# RollerShutterNode_nrf_1-1_EN.net
KiCad netlist of a schematic drawn in EAGLE
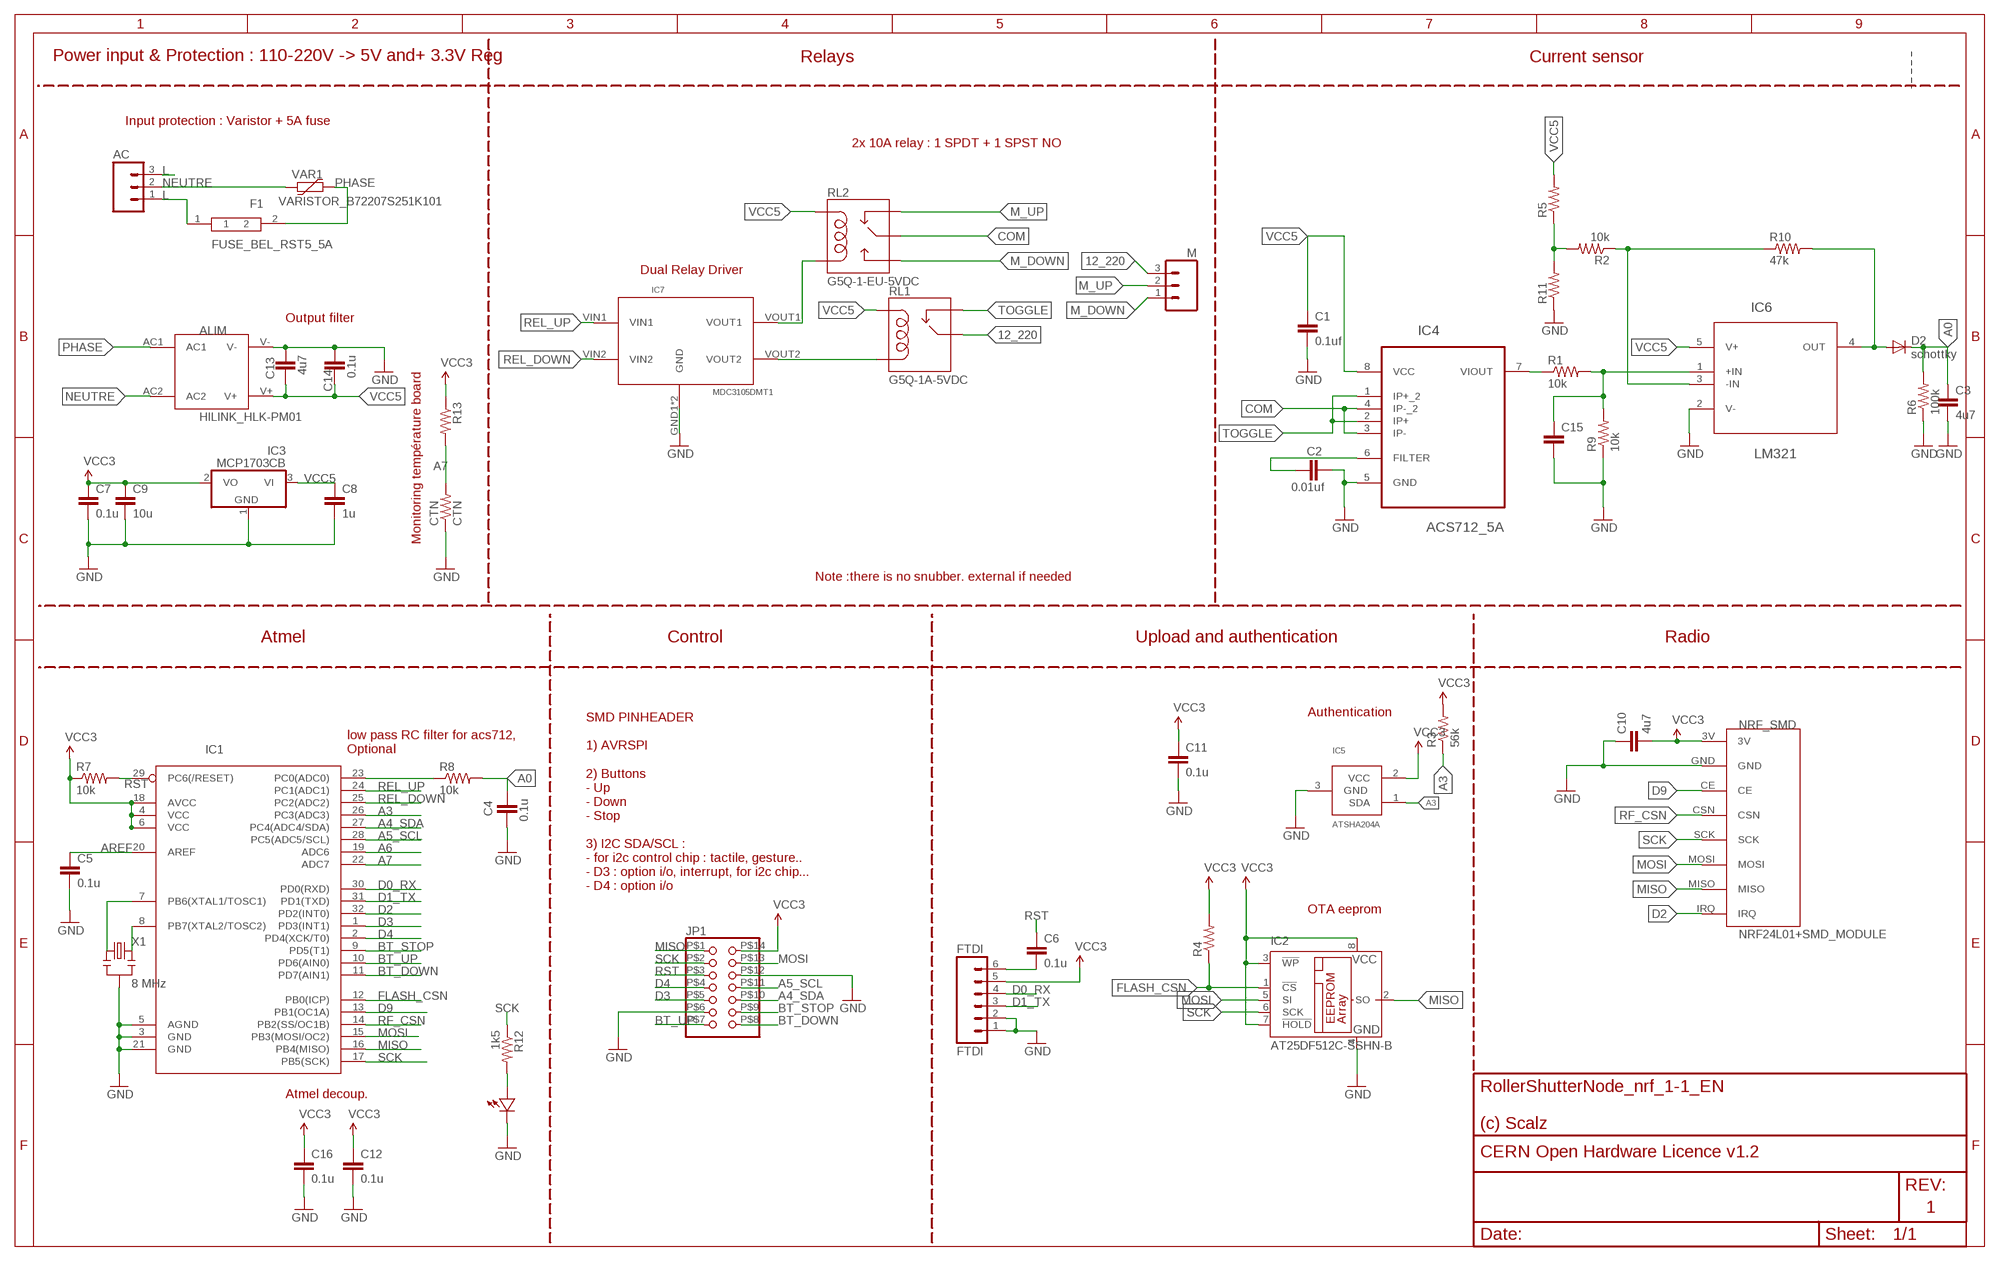
[diagram p0: schematic, sheet 1]

(export (version "E")
  (design (tool "Eeschema 10.0.6"))
  (components
    (comp (ref "AC")
      (value "M03-SCREW-5MM")
      (footprint "eagle-import:SCREWTERMINAL-5MM-3")
      (libsource (lib "eagle-import") (part "M03-SCREW-5MM"))
    )
    (comp (ref "ALIM")
      (value "HILINK_HLK-PM01")
      (footprint "eagle-import:HILINK_HLK-PM01")
      (libsource (lib "eagle-import") (part "HILINK_HLK-PM01"))
    )
    (comp (ref "C1")
      (value "0.1uf")
      (footprint "eagle-import:0805-CAP")
      (libsource (lib "eagle-import") (part "CAP0805-CAP"))
    )
    (comp (ref "C2")
      (value "0.01uf")
      (footprint "eagle-import:0805-CAP")
      (libsource (lib "eagle-import") (part "CAP0805-CAP"))
    )
    (comp (ref "C3")
      (value "4u7")
      (footprint "eagle-import:0805-CAP")
      (libsource (lib "eagle-import") (part "CAP0805-CAP"))
    )
    (comp (ref "C4")
      (value "0.1u")
      (footprint "eagle-import:0805-CAP")
      (libsource (lib "eagle-import") (part "CAP0805-CAP"))
    )
    (comp (ref "C5")
      (value "0.1u")
      (footprint "eagle-import:0805-CAP")
      (libsource (lib "eagle-import") (part "CAP0805-CAP"))
    )
    (comp (ref "C6")
      (value "0.1u")
      (footprint "eagle-import:0805-CAP")
      (libsource (lib "eagle-import") (part "CAP0805-CAP"))
    )
    (comp (ref "C7")
      (value "0.1u")
      (footprint "eagle-import:0805-CAP")
      (libsource (lib "eagle-import") (part "CAP0805-CAP"))
    )
    (comp (ref "C8")
      (value "1u")
      (footprint "eagle-import:0805-CAP")
      (libsource (lib "eagle-import") (part "CAP0805-CAP"))
    )
    (comp (ref "C9")
      (value "10u")
      (footprint "eagle-import:0805-CAP")
      (libsource (lib "eagle-import") (part "CAP0805-CAP"))
    )
    (comp (ref "C10")
      (value "4u7")
      (footprint "eagle-import:0805-CAP")
      (libsource (lib "eagle-import") (part "CAP0805-CAP"))
    )
    (comp (ref "C11")
      (value "0.1u")
      (footprint "eagle-import:0805-CAP")
      (libsource (lib "eagle-import") (part "CAP0805-CAP"))
    )
    (comp (ref "C12")
      (value "0.1u")
      (footprint "eagle-import:0805-CAP")
      (libsource (lib "eagle-import") (part "CAP0805-CAP"))
    )
    (comp (ref "C13")
      (value "4u7")
      (footprint "eagle-import:0805-CAP")
      (libsource (lib "eagle-import") (part "CAP0805-CAP"))
    )
    (comp (ref "C14")
      (value "0.1u")
      (footprint "eagle-import:0805-CAP")
      (libsource (lib "eagle-import") (part "CAP0805-CAP"))
    )
    (comp (ref "C15")
      (value "CAP0805-CAP")
      (footprint "eagle-import:0805-CAP")
      (libsource (lib "eagle-import") (part "CAP0805-CAP"))
    )
    (comp (ref "C16")
      (value "0.1u")
      (footprint "eagle-import:0805-CAP")
      (libsource (lib "eagle-import") (part "CAP0805-CAP"))
    )
    (comp (ref "CTN")
      (value "CTN")
      (footprint "eagle-import:0805-RES")
      (libsource (lib "eagle-import") (part "RESISTOR0805-RES"))
    )
    (comp (ref "D1")
      (value "LED0805")
      (footprint "eagle-import:0805-LED")
      (libsource (lib "eagle-import") (part "LED0805"))
    )
    (comp (ref "D2")
      (value "schottky")
      (footprint "eagle-import:SOD-323")
      (libsource (lib "eagle-import") (part "DIODESOD"))
    )
    (comp (ref "F1")
      (value "FUSE_BEL_RST5_5A")
      (footprint "eagle-import:FUSE_BEL_RST5_5A")
      (libsource (lib "eagle-import") (part "FUSE_BEL_RST5_5A"))
    )
    (comp (ref "FTDI")
      (value "FTDI")
      (footprint "eagle-import:1X06")
      (libsource (lib "eagle-import") (part "M06SIP"))
    )
    (comp (ref "IC1")
      (value "ATMega-328")
      (footprint "eagle-import:TQFP32-08")
      (libsource (lib "eagle-import") (part "ATMEGA168/328TQFP32"))
    )
    (comp (ref "IC2")
      (value "AT25DF512C-SSHN-B")
      (footprint "eagle-import:SO-08")
      (fields (field (name "MF") "MICROCHIP") (field (name "MPN") "25AA080/SN"))
      (libsource (lib "eagle-import") (part "25SNAA080"))
    )
    (comp (ref "IC3")
      (value "MCP1703CB")
      (footprint "eagle-import:SOT23")
      (libsource (lib "eagle-import") (part "MCP1703CB"))
    )
    (comp (ref "IC4")
      (value "ACS712_5A")
      (footprint "eagle-import:SOIC127P600X175-8N")
      (fields (field (name "MPN") "ACS712ELCTR-20A-T"))
      (libsource (lib "eagle-import") (part "ACS712ELCTR-20A-T"))
    )
    (comp (ref "IC5")
      (value "ATSHA204A")
      (footprint "eagle-import:SOT23")
      (libsource (lib "eagle-import") (part "ATSHA204A"))
    )
    (comp (ref "IC6")
      (value "LM321")
      (footprint "eagle-import:SOT95P285X120-5N")
      (fields (field (name "MPN") "LM321MF"))
      (libsource (lib "eagle-import") (part "LM321MF"))
    )
    (comp (ref "IC7")
      (value "MDC3105DMT1")
      (footprint "eagle-import:MDC3105DMT1")
      (libsource (lib "eagle-import") (part "MDC3105DMT1"))
    )
    (comp (ref "JP1")
      (value "PINHD-2X7")
      (footprint "eagle-import:2X07")
      (libsource (lib "eagle-import") (part "PINHD-2X7"))
    )
    (comp (ref "M")
      (value "M03-SCREW-5MM")
      (footprint "eagle-import:SCREWTERMINAL-5MM-3")
      (libsource (lib "eagle-import") (part "M03-SCREW-5MM"))
    )
    (comp (ref "NRF_SMD")
      (value "NRF24L01+SMD_MODULE")
      (footprint "eagle-import:NRF24L01+SMD_MODULE")
      (libsource (lib "eagle-import") (part "NRF24L01+SMD_MODULE"))
    )
    (comp (ref "R1")
      (value "10k")
      (footprint "eagle-import:0805-RES")
      (libsource (lib "eagle-import") (part "RESISTOR0805-RES"))
    )
    (comp (ref "R2")
      (value "10k")
      (footprint "eagle-import:0805-RES")
      (libsource (lib "eagle-import") (part "RESISTOR0805-RES"))
    )
    (comp (ref "R3")
      (value "56k")
      (footprint "eagle-import:0805-RES")
      (libsource (lib "eagle-import") (part "RESISTOR0805-RES"))
    )
    (comp (ref "R4")
      (value "RESISTOR0805-RES")
      (footprint "eagle-import:0805-RES")
      (libsource (lib "eagle-import") (part "RESISTOR0805-RES"))
    )
    (comp (ref "R5")
      (value "RESISTOR0805-RES")
      (footprint "eagle-import:0805-RES")
      (libsource (lib "eagle-import") (part "RESISTOR0805-RES"))
    )
    (comp (ref "R6")
      (value "100k")
      (footprint "eagle-import:0805-RES")
      (libsource (lib "eagle-import") (part "RESISTOR0805-RES"))
    )
    (comp (ref "R7")
      (value "10k")
      (footprint "eagle-import:0805-RES")
      (libsource (lib "eagle-import") (part "RESISTOR0805-RES"))
    )
    (comp (ref "R8")
      (value "10k")
      (footprint "eagle-import:0805-RES")
      (libsource (lib "eagle-import") (part "RESISTOR0805-RES"))
    )
    (comp (ref "R9")
      (value "10k")
      (footprint "eagle-import:0805-RES")
      (libsource (lib "eagle-import") (part "RESISTOR0805-RES"))
    )
    (comp (ref "R10")
      (value "47k")
      (footprint "eagle-import:0805-RES")
      (libsource (lib "eagle-import") (part "RESISTOR0805-RES"))
    )
    (comp (ref "R11")
      (value "RESISTOR0805-RES")
      (footprint "eagle-import:0805-RES")
      (libsource (lib "eagle-import") (part "RESISTOR0805-RES"))
    )
    (comp (ref "R12")
      (value "1k5")
      (footprint "eagle-import:0805-RES")
      (libsource (lib "eagle-import") (part "RESISTOR0805-RES"))
    )
    (comp (ref "R13")
      (value "RESISTOR0805-RES")
      (footprint "eagle-import:0805-RES")
      (libsource (lib "eagle-import") (part "RESISTOR0805-RES"))
    )
    (comp (ref "RL1")
      (value "G5Q-1A-5VDC")
      (footprint "eagle-import:G5Q_SINGLE")
      (libsource (lib "eagle-import") (part "G5Q_SINGLE"))
    )
    (comp (ref "RL2")
      (value "G5Q-1-EU-5VDC")
      (footprint "eagle-import:RELAY-G5Q")
      (libsource (lib "eagle-import") (part "RELAYPTH"))
    )
    (comp (ref "VAR1")
      (value "VARISTOR_B72207S251K101")
      (footprint "eagle-import:VARISTOR_B72207S251K101")
      (libsource (lib "eagle-import") (part "VARISTOR_B72207S251K101"))
    )
    (comp (ref "X1")
      (value "8 MHz")
      (footprint "eagle-import:RESONATOR-SMD")
      (libsource (lib "eagle-import") (part "RESONATORSMD"))
    )
  )
  (nets
    (net (code "1") (name "/A4_SDA") (class "Default")
      (node (ref "IC1") (pin "27") (pinfunction "PC4(ADC4/SDA)_27") (pintype "bidirectional"))
      (node (ref "JP1") (pin "P$10") (pinfunction "10_P$10") (pintype "passive"))
    )
    (net (code "2") (name "/A5_SCL") (class "Default")
      (node (ref "IC1") (pin "28") (pinfunction "PC5(ADC5/SCL)_28") (pintype "bidirectional"))
      (node (ref "JP1") (pin "P$11") (pinfunction "8_P$11") (pintype "passive"))
    )
    (net (code "3") (name "/A6") (class "Default")
      (node (ref "IC1") (pin "19") (pinfunction "ADC6_19") (pintype "bidirectional"))
    )
    (net (code "4") (name "/A7") (class "Default")
      (node (ref "CTN") (pin "2") (pinfunction "2_2") (pintype "passive"))
      (node (ref "IC1") (pin "22") (pinfunction "ADC7_22") (pintype "bidirectional"))
      (node (ref "R13") (pin "2") (pinfunction "2_2") (pintype "passive"))
    )
    (net (code "5") (name "/AREF") (class "Default")
      (node (ref "C5") (pin "1") (pinfunction "1_1") (pintype "passive"))
      (node (ref "IC1") (pin "20") (pinfunction "AREF_20") (pintype "bidirectional"))
    )
    (net (code "6") (name "/BT_DOWN") (class "Default")
      (node (ref "IC1") (pin "11") (pinfunction "PD7(AIN1)_11") (pintype "bidirectional"))
      (node (ref "JP1") (pin "P$8") (pinfunction "14_P$8") (pintype "passive"))
    )
    (net (code "7") (name "/BT_STOP") (class "Default")
      (node (ref "IC1") (pin "9") (pinfunction "PD5(T1)_9") (pintype "bidirectional"))
      (node (ref "JP1") (pin "P$9") (pinfunction "12_P$9") (pintype "passive"))
    )
    (net (code "8") (name "/BT_UP") (class "Default")
      (node (ref "IC1") (pin "10") (pinfunction "PD6(AIN0)_10") (pintype "bidirectional"))
      (node (ref "JP1") (pin "P$7") (pinfunction "13_P$7") (pintype "passive"))
    )
    (net (code "9") (name "/D0_RX") (class "Default")
      (node (ref "FTDI") (pin "4") (pinfunction "4_4") (pintype "passive"))
      (node (ref "IC1") (pin "30") (pinfunction "PD0(RXD)_30") (pintype "bidirectional"))
    )
    (net (code "10") (name "/D1_TX") (class "Default")
      (node (ref "FTDI") (pin "3") (pinfunction "3_3") (pintype "passive"))
      (node (ref "IC1") (pin "31") (pinfunction "PD1(TXD)_31") (pintype "bidirectional"))
    )
    (net (code "11") (name "/D3") (class "Default")
      (node (ref "IC1") (pin "1") (pinfunction "PD3(INT1)_1") (pintype "bidirectional"))
      (node (ref "JP1") (pin "P$5") (pinfunction "9_P$5") (pintype "passive"))
    )
    (net (code "12") (name "/D4") (class "Default")
      (node (ref "IC1") (pin "2") (pinfunction "PD4(XCK/T0)_2") (pintype "bidirectional"))
      (node (ref "JP1") (pin "P$4") (pinfunction "7_P$4") (pintype "passive"))
    )
    (net (code "13") (name "/L") (class "Default")
      (node (ref "AC") (pin "1") (pinfunction "1_1") (pintype "passive"))
      (node (ref "AC") (pin "3") (pinfunction "3_3") (pintype "passive"))
      (node (ref "F1") (pin "1") (pinfunction "1_1") (pintype "bidirectional"))
    )
    (net (code "14") (name "/RST") (class "Default")
      (node (ref "C6") (pin "1") (pinfunction "1_1") (pintype "passive"))
      (node (ref "IC1") (pin "29") (pinfunction "PC6(/RESET)_29") (pintype "bidirectional"))
      (node (ref "JP1") (pin "P$3") (pinfunction "5_P$3") (pintype "passive"))
      (node (ref "R7") (pin "2") (pinfunction "2_2") (pintype "passive"))
    )
    (net (code "15") (name "12_220") (class "Default")
      (node (ref "M") (pin "3") (pinfunction "3_3") (pintype "passive"))
      (node (ref "RL1") (pin "2") (pinfunction "MAIN_2") (pintype "bidirectional"))
    )
    (net (code "16") (name "A0") (class "Default")
      (node (ref "C3") (pin "1") (pinfunction "1_1") (pintype "passive"))
      (node (ref "C4") (pin "2") (pinfunction "2_2") (pintype "passive"))
      (node (ref "D2") (pin "1") (pinfunction "C_1") (pintype "passive"))
      (node (ref "R6") (pin "2") (pinfunction "2_2") (pintype "passive"))
      (node (ref "R8") (pin "2") (pinfunction "2_2") (pintype "passive"))
    )
    (net (code "17") (name "A3") (class "Default")
      (node (ref "IC1") (pin "26") (pinfunction "PC3(ADC3)_26") (pintype "bidirectional"))
      (node (ref "IC5") (pin "1") (pinfunction "SDA_1") (pintype "bidirectional"))
      (node (ref "R3") (pin "1") (pinfunction "1_1") (pintype "passive"))
    )
    (net (code "18") (name "COM") (class "Default")
      (node (ref "IC4") (pin "3") (pinfunction "IP-_3") (pintype "input"))
      (node (ref "IC4") (pin "4") (pinfunction "IP-_2_4") (pintype "input"))
      (node (ref "RL2") (pin "2") (pinfunction "MAIN_2") (pintype "bidirectional"))
    )
    (net (code "19") (name "D2") (class "Default")
      (node (ref "IC1") (pin "32") (pinfunction "PD2(INT0)_32") (pintype "bidirectional"))
      (node (ref "NRF_SMD") (pin "IRQ") (pinfunction "IRQ_IRQ") (pintype "bidirectional"))
    )
    (net (code "20") (name "D9") (class "Default")
      (node (ref "IC1") (pin "13") (pinfunction "PB1(OC1A)_13") (pintype "bidirectional"))
      (node (ref "NRF_SMD") (pin "CE") (pinfunction "CE_CE") (pintype "bidirectional"))
    )
    (net (code "21") (name "FLASH_CSN") (class "Default")
      (node (ref "IC1") (pin "12") (pinfunction "PB0(ICP)_12") (pintype "bidirectional"))
      (node (ref "IC2") (pin "1") (pinfunction "~{CS}_1") (pintype "input"))
      (node (ref "R4") (pin "1") (pinfunction "1_1") (pintype "passive"))
    )
    (net (code "22") (name "GND") (class "Default")
      (node (ref "ALIM") (pin "V-") (pinfunction "V-_V-") (pintype "bidirectional"))
      (node (ref "C1") (pin "2") (pinfunction "2_2") (pintype "passive"))
      (node (ref "C10") (pin "1") (pinfunction "1_1") (pintype "passive"))
      (node (ref "C11") (pin "2") (pinfunction "2_2") (pintype "passive"))
      (node (ref "C12") (pin "2") (pinfunction "2_2") (pintype "passive"))
      (node (ref "C13") (pin "2") (pinfunction "2_2") (pintype "passive"))
      (node (ref "C14") (pin "2") (pinfunction "2_2") (pintype "passive"))
      (node (ref "C15") (pin "2") (pinfunction "2_2") (pintype "passive"))
      (node (ref "C16") (pin "2") (pinfunction "2_2") (pintype "passive"))
      (node (ref "C2") (pin "2") (pinfunction "2_2") (pintype "passive"))
      (node (ref "C3") (pin "2") (pinfunction "2_2") (pintype "passive"))
      (node (ref "C4") (pin "1") (pinfunction "1_1") (pintype "passive"))
      (node (ref "C5") (pin "2") (pinfunction "2_2") (pintype "passive"))
      (node (ref "C7") (pin "2") (pinfunction "2_2") (pintype "passive"))
      (node (ref "C8") (pin "2") (pinfunction "2_2") (pintype "passive"))
      (node (ref "C9") (pin "2") (pinfunction "2_2") (pintype "passive"))
      (node (ref "CTN") (pin "1") (pinfunction "1_1") (pintype "passive"))
      (node (ref "D1") (pin "MINUS") (pinfunction "MINUS_MINUS") (pintype "passive"))
      (node (ref "FTDI") (pin "1") (pinfunction "1_1") (pintype "passive"))
      (node (ref "FTDI") (pin "2") (pinfunction "2_2") (pintype "passive"))
      (node (ref "IC1") (pin "21") (pinfunction "GND_21") (pintype "bidirectional"))
      (node (ref "IC1") (pin "3") (pinfunction "GND_3") (pintype "bidirectional"))
      (node (ref "IC1") (pin "5") (pinfunction "AGND_5") (pintype "bidirectional"))
      (node (ref "IC2") (pin "4") (pinfunction "GND_4") (pintype "power_in"))
      (node (ref "IC3") (pin "1") (pinfunction "GND_1") (pintype "passive"))
      (node (ref "IC4") (pin "5") (pinfunction "GND_5") (pintype "passive"))
      (node (ref "IC5") (pin "3") (pinfunction "GND_3") (pintype "bidirectional"))
      (node (ref "IC6") (pin "2") (pinfunction "V-_2") (pintype "power_in"))
      (node (ref "IC7") (pin "GND1") (pinfunction "GND_GND1") (pintype "bidirectional"))
      (node (ref "IC7") (pin "GND2") (pinfunction "GND_GND2") (pintype "bidirectional"))
      (node (ref "JP1") (pin "P$12") (pinfunction "6_P$12") (pintype "passive"))
      (node (ref "JP1") (pin "P$6") (pinfunction "11_P$6") (pintype "passive"))
      (node (ref "NRF_SMD") (pin "GND") (pinfunction "GND_GND") (pintype "bidirectional"))
      (node (ref "R11") (pin "1") (pinfunction "1_1") (pintype "passive"))
      (node (ref "R6") (pin "1") (pinfunction "1_1") (pintype "passive"))
      (node (ref "R9") (pin "1") (pinfunction "1_1") (pintype "passive"))
      (node (ref "X1") (pin "2") (pinfunction "2_2") (pintype "passive"))
    )
    (net (code "23") (name "MISO") (class "Default")
      (node (ref "IC1") (pin "16") (pinfunction "PB4(MISO)_16") (pintype "bidirectional"))
      (node (ref "IC2") (pin "2") (pinfunction "SO_2") (pintype "bidirectional"))
      (node (ref "JP1") (pin "P$1") (pinfunction "1_P$1") (pintype "passive"))
      (node (ref "NRF_SMD") (pin "MISO") (pinfunction "MISO_MISO") (pintype "bidirectional"))
    )
    (net (code "24") (name "MOSI") (class "Default")
      (node (ref "IC1") (pin "15") (pinfunction "PB3(MOSI/OC2)_15") (pintype "bidirectional"))
      (node (ref "IC2") (pin "5") (pinfunction "SI_5") (pintype "input"))
      (node (ref "JP1") (pin "P$13") (pinfunction "4_P$13") (pintype "passive"))
      (node (ref "NRF_SMD") (pin "MOSI") (pinfunction "MOSI_MOSI") (pintype "bidirectional"))
    )
    (net (code "25") (name "M_DOWN") (class "Default")
      (node (ref "M") (pin "1") (pinfunction "1_1") (pintype "passive"))
      (node (ref "RL2") (pin "3") (pinfunction "NO_3") (pintype "bidirectional"))
    )
    (net (code "26") (name "M_UP") (class "Default")
      (node (ref "M") (pin "2") (pinfunction "2_2") (pintype "passive"))
      (node (ref "RL2") (pin "4") (pinfunction "NC_4") (pintype "bidirectional"))
    )
    (net (code "27") (name "NEUTRE") (class "Default")
      (node (ref "AC") (pin "2") (pinfunction "2_2") (pintype "passive"))
      (node (ref "ALIM") (pin "AC2") (pinfunction "AC2_AC2") (pintype "bidirectional"))
      (node (ref "VAR1") (pin "1") (pinfunction "1_1") (pintype "passive"))
    )
    (net (code "28") (name "Net-(C6-Pad2)") (class "Default")
      (node (ref "C6") (pin "2") (pinfunction "2_2") (pintype "passive"))
      (node (ref "FTDI") (pin "6") (pinfunction "6_6") (pintype "passive"))
    )
    (net (code "29") (name "Net-(D1-PadPLUS)") (class "Default")
      (node (ref "D1") (pin "PLUS") (pinfunction "PLUS_PLUS") (pintype "passive"))
      (node (ref "R12") (pin "2") (pinfunction "2_2") (pintype "passive"))
    )
    (net (code "30") (name "Net-(D2-A)") (class "Default")
      (node (ref "D2") (pin "2") (pinfunction "A_2") (pintype "passive"))
      (node (ref "IC6") (pin "4") (pinfunction "OUT_4") (pintype "output"))
      (node (ref "R10") (pin "2") (pinfunction "2_2") (pintype "passive"))
    )
    (net (code "31") (name "Net-(IC1-PB6(XTAL1{slash}TOSC1))") (class "Default")
      (node (ref "IC1") (pin "7") (pinfunction "PB6(XTAL1/TOSC1)_7") (pintype "bidirectional"))
      (node (ref "X1") (pin "1") (pinfunction "1_1") (pintype "passive"))
    )
    (net (code "32") (name "Net-(IC1-PB7(XTAL2{slash}TOSC2))") (class "Default")
      (node (ref "IC1") (pin "8") (pinfunction "PB7(XTAL2/TOSC2)_8") (pintype "bidirectional"))
      (node (ref "X1") (pin "3") (pinfunction "3_3") (pintype "passive"))
    )
    (net (code "33") (name "Net-(IC1-PC0(ADC0))") (class "Default")
      (node (ref "IC1") (pin "23") (pinfunction "PC0(ADC0)_23") (pintype "bidirectional"))
      (node (ref "R8") (pin "1") (pinfunction "1_1") (pintype "passive"))
    )
    (net (code "34") (name "Net-(IC4-FILTER)") (class "Default")
      (node (ref "C2") (pin "1") (pinfunction "1_1") (pintype "passive"))
      (node (ref "IC4") (pin "6") (pinfunction "FILTER_6") (pintype "input"))
    )
    (net (code "35") (name "Net-(IC4-VIOUT)") (class "Default")
      (node (ref "IC4") (pin "7") (pinfunction "VIOUT_7") (pintype "output"))
      (node (ref "R1") (pin "1") (pinfunction "1_1") (pintype "passive"))
    )
    (net (code "36") (name "Net-(IC6-+IN)") (class "Default")
      (node (ref "C15") (pin "1") (pinfunction "1_1") (pintype "passive"))
      (node (ref "IC6") (pin "1") (pinfunction "+IN_1") (pintype "input"))
      (node (ref "R1") (pin "2") (pinfunction "2_2") (pintype "passive"))
      (node (ref "R9") (pin "2") (pinfunction "2_2") (pintype "passive"))
    )
    (net (code "37") (name "Net-(IC6--IN)") (class "Default")
      (node (ref "IC6") (pin "3") (pinfunction "-IN_3") (pintype "input"))
      (node (ref "R10") (pin "1") (pinfunction "1_1") (pintype "passive"))
      (node (ref "R2") (pin "1") (pinfunction "1_1") (pintype "passive"))
    )
    (net (code "38") (name "Net-(R11-Pad2)") (class "Default")
      (node (ref "R11") (pin "2") (pinfunction "2_2") (pintype "passive"))
      (node (ref "R2") (pin "2") (pinfunction "2_2") (pintype "passive"))
      (node (ref "R5") (pin "1") (pinfunction "1_1") (pintype "passive"))
    )
    (net (code "39") (name "Net-(RL1-COIL2)") (class "Default")
      (node (ref "IC7") (pin "VOUT2") (pinfunction "VOUT2_VOUT2") (pintype "bidirectional"))
      (node (ref "RL1") (pin "5") (pinfunction "COIL2_5") (pintype "bidirectional"))
    )
    (net (code "40") (name "Net-(RL2-COIL2)") (class "Default")
      (node (ref "IC7") (pin "VOUT1") (pinfunction "VOUT1_VOUT1") (pintype "bidirectional"))
      (node (ref "RL2") (pin "1") (pinfunction "COIL2_1") (pintype "bidirectional"))
    )
    (net (code "41") (name "PHASE") (class "Default")
      (node (ref "ALIM") (pin "AC1") (pinfunction "AC1_AC1") (pintype "bidirectional"))
      (node (ref "F1") (pin "2") (pinfunction "2_2") (pintype "bidirectional"))
      (node (ref "VAR1") (pin "2") (pinfunction "2_2") (pintype "passive"))
    )
    (net (code "42") (name "REL_DOWN") (class "Default")
      (node (ref "IC1") (pin "25") (pinfunction "PC2(ADC2)_25") (pintype "bidirectional"))
      (node (ref "IC7") (pin "VIN2") (pinfunction "VIN2_VIN2") (pintype "bidirectional"))
    )
    (net (code "43") (name "REL_UP") (class "Default")
      (node (ref "IC1") (pin "24") (pinfunction "PC1(ADC1)_24") (pintype "bidirectional"))
      (node (ref "IC7") (pin "VIN1") (pinfunction "VIN1_VIN1") (pintype "bidirectional"))
    )
    (net (code "44") (name "RF_CSN") (class "Default")
      (node (ref "IC1") (pin "14") (pinfunction "PB2(SS/OC1B)_14") (pintype "bidirectional"))
      (node (ref "NRF_SMD") (pin "CSN") (pinfunction "CSN_CSN") (pintype "bidirectional"))
    )
    (net (code "45") (name "SCK") (class "Default")
      (node (ref "IC1") (pin "17") (pinfunction "PB5(SCK)_17") (pintype "bidirectional"))
      (node (ref "IC2") (pin "6") (pinfunction "SCK_6") (pintype "input"))
      (node (ref "JP1") (pin "P$2") (pinfunction "3_P$2") (pintype "passive"))
      (node (ref "NRF_SMD") (pin "SCK") (pinfunction "SCK_SCK") (pintype "bidirectional"))
      (node (ref "R12") (pin "1") (pinfunction "1_1") (pintype "passive"))
    )
    (net (code "46") (name "TOGGLE") (class "Default")
      (node (ref "IC4") (pin "1") (pinfunction "IP+_2_1") (pintype "input"))
      (node (ref "IC4") (pin "2") (pinfunction "IP+_2") (pintype "input"))
      (node (ref "RL1") (pin "3") (pinfunction "NC_3") (pintype "bidirectional"))
    )
    (net (code "47") (name "VCC3") (class "Default")
      (node (ref "C10") (pin "2") (pinfunction "2_2") (pintype "passive"))
      (node (ref "C11") (pin "1") (pinfunction "1_1") (pintype "passive"))
      (node (ref "C12") (pin "1") (pinfunction "1_1") (pintype "passive"))
      (node (ref "C16") (pin "1") (pinfunction "1_1") (pintype "passive"))
      (node (ref "C7") (pin "1") (pinfunction "1_1") (pintype "passive"))
      (node (ref "C9") (pin "1") (pinfunction "1_1") (pintype "passive"))
      (node (ref "FTDI") (pin "5") (pinfunction "5_5") (pintype "passive"))
      (node (ref "IC1") (pin "18") (pinfunction "AVCC_18") (pintype "bidirectional"))
      (node (ref "IC1") (pin "4") (pinfunction "VCC_4") (pintype "bidirectional"))
      (node (ref "IC1") (pin "6") (pinfunction "VCC_6") (pintype "bidirectional"))
      (node (ref "IC2") (pin "3") (pinfunction "~{WP}_3") (pintype "input"))
      (node (ref "IC2") (pin "7") (pinfunction "~{HOLD}_7") (pintype "input"))
      (node (ref "IC2") (pin "8") (pinfunction "VCC_8") (pintype "power_in"))
      (node (ref "IC3") (pin "2") (pinfunction "VO_2") (pintype "passive"))
      (node (ref "IC5") (pin "2") (pinfunction "VCC_2") (pintype "bidirectional"))
      (node (ref "JP1") (pin "P$14") (pinfunction "2_P$14") (pintype "passive"))
      (node (ref "NRF_SMD") (pin "3V") (pinfunction "3V_3V") (pintype "bidirectional"))
      (node (ref "R13") (pin "1") (pinfunction "1_1") (pintype "passive"))
      (node (ref "R3") (pin "2") (pinfunction "2_2") (pintype "passive"))
      (node (ref "R4") (pin "2") (pinfunction "2_2") (pintype "passive"))
      (node (ref "R7") (pin "1") (pinfunction "1_1") (pintype "passive"))
    )
    (net (code "48") (name "VCC5") (class "Default")
      (node (ref "ALIM") (pin "V+") (pinfunction "V+_V+") (pintype "bidirectional"))
      (node (ref "C1") (pin "1") (pinfunction "1_1") (pintype "passive"))
      (node (ref "C13") (pin "1") (pinfunction "1_1") (pintype "passive"))
      (node (ref "C14") (pin "1") (pinfunction "1_1") (pintype "passive"))
      (node (ref "C8") (pin "1") (pinfunction "1_1") (pintype "passive"))
      (node (ref "IC3") (pin "3") (pinfunction "VI_3") (pintype "input"))
      (node (ref "IC4") (pin "8") (pinfunction "VCC_8") (pintype "power_in"))
      (node (ref "IC6") (pin "5") (pinfunction "V+_5") (pintype "power_in"))
      (node (ref "R5") (pin "2") (pinfunction "2_2") (pintype "passive"))
      (node (ref "RL1") (pin "1") (pinfunction "COIL1_1") (pintype "bidirectional"))
      (node (ref "RL2") (pin "5") (pinfunction "COIL1_5") (pintype "bidirectional"))
    )
  )
)
